# PSC_LED_KEYBOARD.net
KiCad netlist of a schematic drawn in Altium Designer
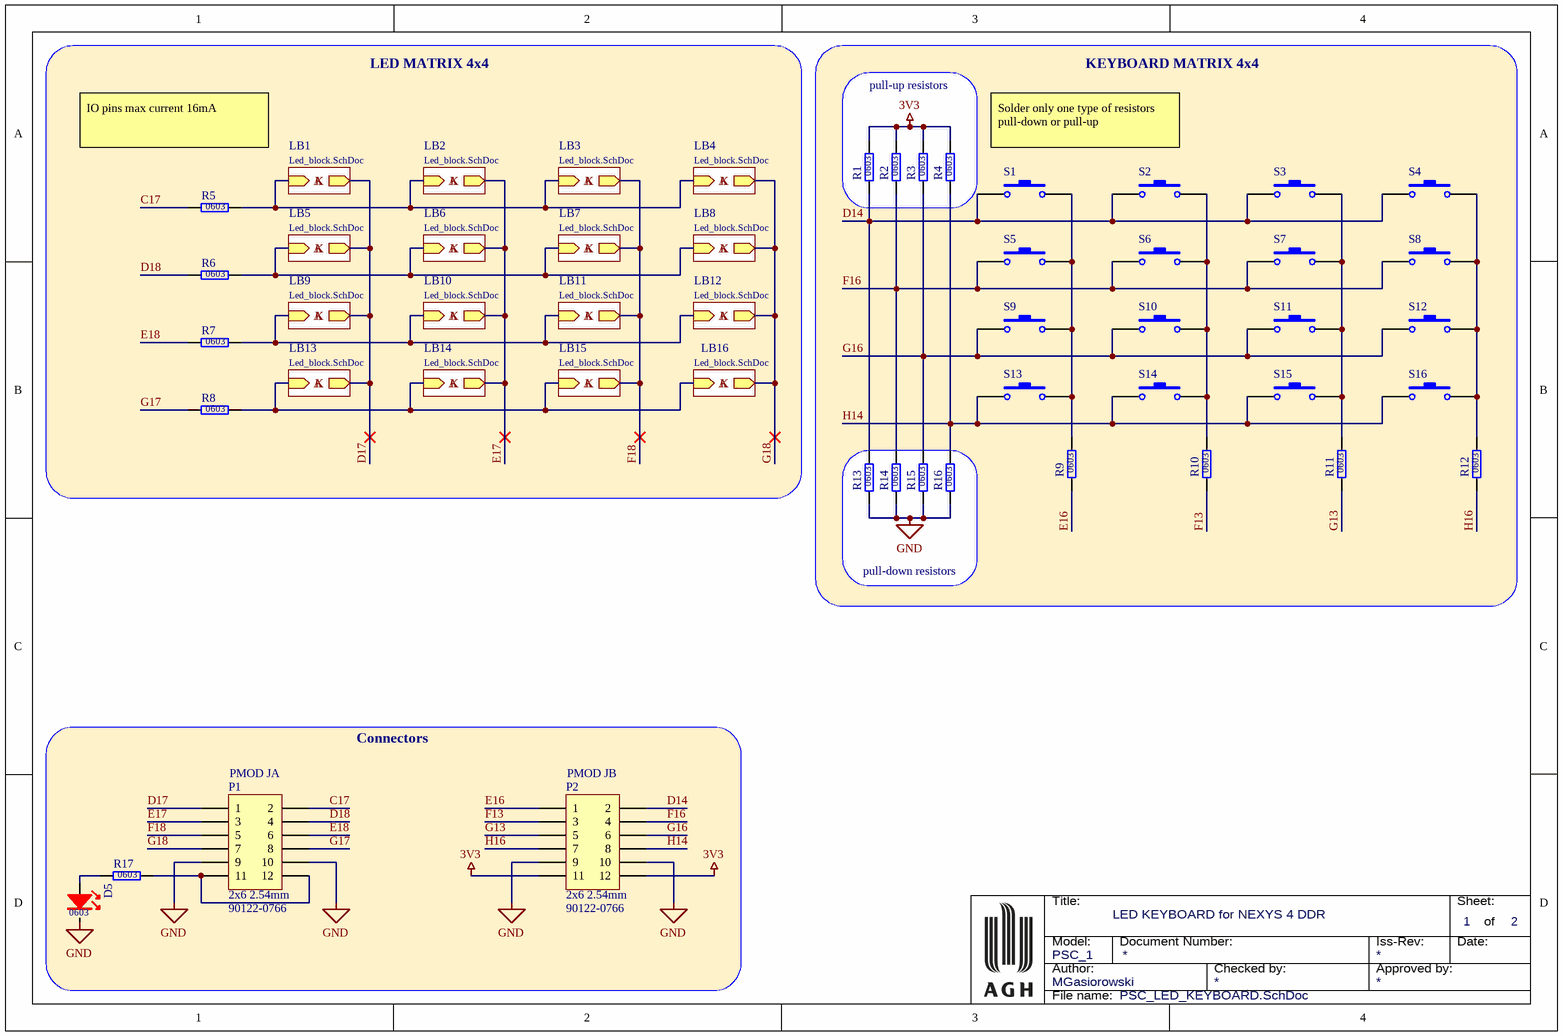
[diagram p0: PSC_LED_KEYBOARD.SchDoc]

(export (version "E")
  (design (tool "Eeschema 10.0.6"))
  (components
    (comp (ref "D5")
      (value "Red LED 0603")
      (footprint "OL_0603_1608")
      (description "LED_RED")
      (fields
        (field (name "SCH_FOOTPRINT") "0603")
        (field (name "PART NUMBER") "OL_R_0603_LTST-C193KRKT-5A")
        (field (name "MANUFACTURER") "Lite-On")
      )
      (libsource (lib "Library") (part "OL_R"))
    )
    (comp (ref "P1")
      (value "90122-0766")
      (footprint "P_HEADER_2x6_2.54_RIGHT_ANGLE")
      (description "Pin Header")
      (fields
        (field (name "SCH_FOOTPRINT") "2x6 2.54mm")
        (field (name "PART NUMBER") "P_HEADER_2x6_2.54_ANGLE")
        (field (name "MANUFACTURER") "Molex")
      )
      (libsource (lib "Library") (part "P_HEADER_2x6"))
    )
    (comp (ref "P2")
      (value "90122-0766")
      (footprint "P_HEADER_2x6_2.54_RIGHT_ANGLE")
      (description "Pin Header")
      (fields
        (field (name "SCH_FOOTPRINT") "2x6 2.54mm")
        (field (name "PART NUMBER") "P_HEADER_2x6_2.54_ANGLE")
        (field (name "MANUFACTURER") "Molex")
      )
      (libsource (lib "Library") (part "P_HEADER_2x6"))
    )
    (comp (ref "R1")
      (value "Resistor")
      (footprint "R_0603_1608")
      (fields
        (field (name "SCH_FOOTPRINT") "0603")
        (field (name "PART NUMBER") "R_10k_0603_0.1")
        (field (name "VOLTAGE") "75V")
        (field (name "POWER") "100mW")
      )
      (libsource (lib "Library") (part "R"))
    )
    (comp (ref "R2")
      (value "Resistor")
      (footprint "R_0603_1608")
      (fields
        (field (name "SCH_FOOTPRINT") "0603")
        (field (name "PART NUMBER") "R_10k_0603_0.1")
        (field (name "VOLTAGE") "75V")
        (field (name "POWER") "100mW")
      )
      (libsource (lib "Library") (part "R"))
    )
    (comp (ref "R3")
      (value "Resistor")
      (footprint "R_0603_1608")
      (fields
        (field (name "SCH_FOOTPRINT") "0603")
        (field (name "PART NUMBER") "R_10k_0603_0.1")
        (field (name "VOLTAGE") "75V")
        (field (name "POWER") "100mW")
      )
      (libsource (lib "Library") (part "R"))
    )
    (comp (ref "R4")
      (value "Resistor")
      (footprint "R_0603_1608")
      (fields
        (field (name "SCH_FOOTPRINT") "0603")
        (field (name "PART NUMBER") "R_10k_0603_0.1")
        (field (name "VOLTAGE") "75V")
        (field (name "POWER") "100mW")
      )
      (libsource (lib "Library") (part "R"))
    )
    (comp (ref "R5")
      (value "Resistor")
      (footprint "R_0603_1608")
      (fields
        (field (name "SCH_FOOTPRINT") "0603")
        (field (name "PART NUMBER") "R_10k_0603_0.1")
        (field (name "VOLTAGE") "75V")
        (field (name "POWER") "100mW")
      )
      (libsource (lib "Library") (part "R"))
    )
    (comp (ref "R6")
      (value "Resistor")
      (footprint "R_0603_1608")
      (fields
        (field (name "SCH_FOOTPRINT") "0603")
        (field (name "PART NUMBER") "R_10k_0603_0.1")
        (field (name "VOLTAGE") "75V")
        (field (name "POWER") "100mW")
      )
      (libsource (lib "Library") (part "R"))
    )
    (comp (ref "R7")
      (value "Resistor")
      (footprint "R_0603_1608")
      (fields
        (field (name "SCH_FOOTPRINT") "0603")
        (field (name "PART NUMBER") "R_10k_0603_0.1")
        (field (name "VOLTAGE") "75V")
        (field (name "POWER") "100mW")
      )
      (libsource (lib "Library") (part "R"))
    )
    (comp (ref "R8")
      (value "Resistor")
      (footprint "R_0603_1608")
      (fields
        (field (name "SCH_FOOTPRINT") "0603")
        (field (name "PART NUMBER") "R_10k_0603_0.1")
        (field (name "VOLTAGE") "75V")
        (field (name "POWER") "100mW")
      )
      (libsource (lib "Library") (part "R"))
    )
    (comp (ref "R9")
      (value "Resistor")
      (footprint "R_0603_1608")
      (fields
        (field (name "SCH_FOOTPRINT") "0603")
        (field (name "PART NUMBER") "R_10k_0603_0.1")
        (field (name "VOLTAGE") "75V")
        (field (name "POWER") "100mW")
      )
      (libsource (lib "Library") (part "R"))
    )
    (comp (ref "R10")
      (value "Resistor")
      (footprint "R_0603_1608")
      (fields
        (field (name "SCH_FOOTPRINT") "0603")
        (field (name "PART NUMBER") "R_10k_0603_0.1")
        (field (name "VOLTAGE") "75V")
        (field (name "POWER") "100mW")
      )
      (libsource (lib "Library") (part "R"))
    )
    (comp (ref "R11")
      (value "Resistor")
      (footprint "R_0603_1608")
      (fields
        (field (name "SCH_FOOTPRINT") "0603")
        (field (name "PART NUMBER") "R_10k_0603_0.1")
        (field (name "VOLTAGE") "75V")
        (field (name "POWER") "100mW")
      )
      (libsource (lib "Library") (part "R"))
    )
    (comp (ref "R12")
      (value "Resistor")
      (footprint "R_0603_1608")
      (fields
        (field (name "SCH_FOOTPRINT") "0603")
        (field (name "PART NUMBER") "R_10k_0603_0.1")
        (field (name "VOLTAGE") "75V")
        (field (name "POWER") "100mW")
      )
      (libsource (lib "Library") (part "R"))
    )
    (comp (ref "R13")
      (value "Resistor")
      (footprint "R_0603_1608")
      (fields
        (field (name "SCH_FOOTPRINT") "0603")
        (field (name "PART NUMBER") "R_10k_0603_0.1")
        (field (name "VOLTAGE") "75V")
        (field (name "POWER") "100mW")
      )
      (libsource (lib "Library") (part "R"))
    )
    (comp (ref "R14")
      (value "Resistor")
      (footprint "R_0603_1608")
      (fields
        (field (name "SCH_FOOTPRINT") "0603")
        (field (name "PART NUMBER") "R_10k_0603_0.1")
        (field (name "VOLTAGE") "75V")
        (field (name "POWER") "100mW")
      )
      (libsource (lib "Library") (part "R"))
    )
    (comp (ref "R15")
      (value "Resistor")
      (footprint "R_0603_1608")
      (fields
        (field (name "SCH_FOOTPRINT") "0603")
        (field (name "PART NUMBER") "R_10k_0603_0.1")
        (field (name "VOLTAGE") "75V")
        (field (name "POWER") "100mW")
      )
      (libsource (lib "Library") (part "R"))
    )
    (comp (ref "R16")
      (value "Resistor")
      (footprint "R_0603_1608")
      (fields
        (field (name "SCH_FOOTPRINT") "0603")
        (field (name "PART NUMBER") "R_10k_0603_0.1")
        (field (name "VOLTAGE") "75V")
        (field (name "POWER") "100mW")
      )
      (libsource (lib "Library") (part "R"))
    )
    (comp (ref "R17")
      (value "Resistor")
      (footprint "R_0603_1608")
      (fields
        (field (name "SCH_FOOTPRINT") "0603")
        (field (name "PART NUMBER") "R_10k_0603_0.1")
        (field (name "VOLTAGE") "75V")
        (field (name "POWER") "100mW")
      )
      (libsource (lib "Library") (part "R"))
    )
    (comp (ref "S1")
      (value "S_TACTSWITCH")
      (footprint "S_TactSwitch_12x12")
      (description "Tact switch")
      (libsource (lib "GG_LIB") (part "S_TACTSWITCH"))
    )
    (comp (ref "S2")
      (value "S_TACTSWITCH")
      (footprint "S_TactSwitch_12x12")
      (description "Tact switch")
      (libsource (lib "GG_LIB") (part "S_TACTSWITCH"))
    )
    (comp (ref "S3")
      (value "S_TACTSWITCH")
      (footprint "S_TactSwitch_12x12")
      (description "Tact switch")
      (libsource (lib "GG_LIB") (part "S_TACTSWITCH"))
    )
    (comp (ref "S4")
      (value "S_TACTSWITCH")
      (footprint "S_TactSwitch_12x12")
      (description "Tact switch")
      (libsource (lib "GG_LIB") (part "S_TACTSWITCH"))
    )
    (comp (ref "S5")
      (value "S_TACTSWITCH")
      (footprint "S_TactSwitch_12x12")
      (description "Tact switch")
      (libsource (lib "GG_LIB") (part "S_TACTSWITCH"))
    )
    (comp (ref "S6")
      (value "S_TACTSWITCH")
      (footprint "S_TactSwitch_12x12")
      (description "Tact switch")
      (libsource (lib "GG_LIB") (part "S_TACTSWITCH"))
    )
    (comp (ref "S7")
      (value "S_TACTSWITCH")
      (footprint "S_TactSwitch_12x12")
      (description "Tact switch")
      (libsource (lib "GG_LIB") (part "S_TACTSWITCH"))
    )
    (comp (ref "S8")
      (value "S_TACTSWITCH")
      (footprint "S_TactSwitch_12x12")
      (description "Tact switch")
      (libsource (lib "GG_LIB") (part "S_TACTSWITCH"))
    )
    (comp (ref "S9")
      (value "S_TACTSWITCH")
      (footprint "S_TactSwitch_12x12")
      (description "Tact switch")
      (libsource (lib "GG_LIB") (part "S_TACTSWITCH"))
    )
    (comp (ref "S10")
      (value "S_TACTSWITCH")
      (footprint "S_TactSwitch_12x12")
      (description "Tact switch")
      (libsource (lib "GG_LIB") (part "S_TACTSWITCH"))
    )
    (comp (ref "S11")
      (value "S_TACTSWITCH")
      (footprint "S_TactSwitch_12x12")
      (description "Tact switch")
      (libsource (lib "GG_LIB") (part "S_TACTSWITCH"))
    )
    (comp (ref "S12")
      (value "S_TACTSWITCH")
      (footprint "S_TactSwitch_12x12")
      (description "Tact switch")
      (libsource (lib "GG_LIB") (part "S_TACTSWITCH"))
    )
    (comp (ref "S13")
      (value "S_TACTSWITCH")
      (footprint "S_TactSwitch_12x12")
      (description "Tact switch")
      (libsource (lib "GG_LIB") (part "S_TACTSWITCH"))
    )
    (comp (ref "S14")
      (value "S_TACTSWITCH")
      (footprint "S_TactSwitch_12x12")
      (description "Tact switch")
      (libsource (lib "GG_LIB") (part "S_TACTSWITCH"))
    )
    (comp (ref "S15")
      (value "S_TACTSWITCH")
      (footprint "S_TactSwitch_12x12")
      (description "Tact switch")
      (libsource (lib "GG_LIB") (part "S_TACTSWITCH"))
    )
    (comp (ref "S16")
      (value "S_TACTSWITCH")
      (footprint "S_TactSwitch_12x12")
      (description "Tact switch")
      (libsource (lib "GG_LIB") (part "S_TACTSWITCH"))
    )
  )
  (nets
    (net (code "1") (name "/A") (class "Default")
      (node (ref "R8") (pin "2") (pinfunction "2_2") (pintype "passive"))
    )
    (net (code "2") (name "/A_1") (class "Default")
      (node (ref "R5") (pin "2") (pinfunction "2_2") (pintype "passive"))
    )
    (net (code "3") (name "/A_2") (class "Default")
      (node (ref "R6") (pin "2") (pinfunction "2_2") (pintype "passive"))
    )
    (net (code "4") (name "/A_3") (class "Default")
      (node (ref "R7") (pin "2") (pinfunction "2_2") (pintype "passive"))
    )
    (net (code "5") (name "/C17") (class "Default")
      (node (ref "P1") (pin "2") (pinfunction "2_2") (pintype "passive"))
      (node (ref "R5") (pin "1") (pinfunction "1_1") (pintype "passive"))
    )
    (net (code "6") (name "/D14") (class "Default")
      (node (ref "P2") (pin "2") (pinfunction "2_2") (pintype "passive"))
      (node (ref "R1") (pin "1") (pinfunction "1_1") (pintype "passive"))
      (node (ref "R13") (pin "2") (pinfunction "2_2") (pintype "passive"))
      (node (ref "S1") (pin "1") (pinfunction "1_1") (pintype "passive"))
      (node (ref "S2") (pin "1") (pinfunction "1_1") (pintype "passive"))
      (node (ref "S3") (pin "1") (pinfunction "1_1") (pintype "passive"))
      (node (ref "S4") (pin "1") (pinfunction "1_1") (pintype "passive"))
    )
    (net (code "7") (name "/D17") (class "Default")
      (node (ref "P1") (pin "1") (pinfunction "1_1") (pintype "passive"))
    )
    (net (code "8") (name "/D18") (class "Default")
      (node (ref "P1") (pin "4") (pinfunction "4_4") (pintype "passive"))
      (node (ref "R6") (pin "1") (pinfunction "1_1") (pintype "passive"))
    )
    (net (code "9") (name "/E16") (class "Default")
      (node (ref "P2") (pin "1") (pinfunction "1_1") (pintype "passive"))
      (node (ref "R9") (pin "1") (pinfunction "1_1") (pintype "passive"))
    )
    (net (code "10") (name "/E17") (class "Default")
      (node (ref "P1") (pin "3") (pinfunction "3_3") (pintype "passive"))
    )
    (net (code "11") (name "/E18") (class "Default")
      (node (ref "P1") (pin "6") (pinfunction "6_6") (pintype "passive"))
      (node (ref "R7") (pin "1") (pinfunction "1_1") (pintype "passive"))
    )
    (net (code "12") (name "/F13") (class "Default")
      (node (ref "P2") (pin "3") (pinfunction "3_3") (pintype "passive"))
      (node (ref "R10") (pin "1") (pinfunction "1_1") (pintype "passive"))
    )
    (net (code "13") (name "/F16") (class "Default")
      (node (ref "P2") (pin "4") (pinfunction "4_4") (pintype "passive"))
      (node (ref "R14") (pin "2") (pinfunction "2_2") (pintype "passive"))
      (node (ref "R2") (pin "1") (pinfunction "1_1") (pintype "passive"))
      (node (ref "S5") (pin "1") (pinfunction "1_1") (pintype "passive"))
      (node (ref "S6") (pin "1") (pinfunction "1_1") (pintype "passive"))
      (node (ref "S7") (pin "1") (pinfunction "1_1") (pintype "passive"))
      (node (ref "S8") (pin "1") (pinfunction "1_1") (pintype "passive"))
    )
    (net (code "14") (name "/F18") (class "Default")
      (node (ref "P1") (pin "5") (pinfunction "5_5") (pintype "passive"))
    )
    (net (code "15") (name "/G13") (class "Default")
      (node (ref "P2") (pin "5") (pinfunction "5_5") (pintype "passive"))
      (node (ref "R11") (pin "1") (pinfunction "1_1") (pintype "passive"))
    )
    (net (code "16") (name "/G16") (class "Default")
      (node (ref "P2") (pin "6") (pinfunction "6_6") (pintype "passive"))
      (node (ref "R15") (pin "2") (pinfunction "2_2") (pintype "passive"))
      (node (ref "R3") (pin "1") (pinfunction "1_1") (pintype "passive"))
      (node (ref "S10") (pin "1") (pinfunction "1_1") (pintype "passive"))
      (node (ref "S11") (pin "1") (pinfunction "1_1") (pintype "passive"))
      (node (ref "S12") (pin "1") (pinfunction "1_1") (pintype "passive"))
      (node (ref "S9") (pin "1") (pinfunction "1_1") (pintype "passive"))
    )
    (net (code "17") (name "/G17") (class "Default")
      (node (ref "P1") (pin "8") (pinfunction "8_8") (pintype "passive"))
      (node (ref "R8") (pin "1") (pinfunction "1_1") (pintype "passive"))
    )
    (net (code "18") (name "/G18") (class "Default")
      (node (ref "P1") (pin "7") (pinfunction "7_7") (pintype "passive"))
    )
    (net (code "19") (name "/H14") (class "Default")
      (node (ref "P2") (pin "8") (pinfunction "8_8") (pintype "passive"))
      (node (ref "R16") (pin "2") (pinfunction "2_2") (pintype "passive"))
      (node (ref "R4") (pin "1") (pinfunction "1_1") (pintype "passive"))
      (node (ref "S13") (pin "1") (pinfunction "1_1") (pintype "passive"))
      (node (ref "S14") (pin "1") (pinfunction "1_1") (pintype "passive"))
      (node (ref "S15") (pin "1") (pinfunction "1_1") (pintype "passive"))
      (node (ref "S16") (pin "1") (pinfunction "1_1") (pintype "passive"))
    )
    (net (code "20") (name "/H16") (class "Default")
      (node (ref "P2") (pin "7") (pinfunction "7_7") (pintype "passive"))
      (node (ref "R12") (pin "1") (pinfunction "1_1") (pintype "passive"))
    )
    (net (code "21") (name "3V3") (class "Default")
      (node (ref "P2") (pin "11") (pinfunction "11_11") (pintype "passive"))
      (node (ref "P2") (pin "12") (pinfunction "12_12") (pintype "passive"))
      (node (ref "R1") (pin "2") (pinfunction "2_2") (pintype "passive"))
      (node (ref "R2") (pin "2") (pinfunction "2_2") (pintype "passive"))
      (node (ref "R3") (pin "2") (pinfunction "2_2") (pintype "passive"))
      (node (ref "R4") (pin "2") (pinfunction "2_2") (pintype "passive"))
    )
    (net (code "22") (name "GND") (class "Default")
      (node (ref "D5") (pin "1") (pinfunction "K_1") (pintype "passive"))
      (node (ref "P1") (pin "10") (pinfunction "10_10") (pintype "passive"))
      (node (ref "P1") (pin "9") (pinfunction "9_9") (pintype "passive"))
      (node (ref "P2") (pin "10") (pinfunction "10_10") (pintype "passive"))
      (node (ref "P2") (pin "9") (pinfunction "9_9") (pintype "passive"))
      (node (ref "R13") (pin "1") (pinfunction "1_1") (pintype "passive"))
      (node (ref "R14") (pin "1") (pinfunction "1_1") (pintype "passive"))
      (node (ref "R15") (pin "1") (pinfunction "1_1") (pintype "passive"))
      (node (ref "R16") (pin "1") (pinfunction "1_1") (pintype "passive"))
    )
    (net (code "23") (name "Net-(D5-A)") (class "Default")
      (node (ref "D5") (pin "2") (pinfunction "A_2") (pintype "passive"))
      (node (ref "R17") (pin "1") (pinfunction "1_1") (pintype "passive"))
    )
    (net (code "24") (name "Net-(P1-Pad11)") (class "Default")
      (node (ref "P1") (pin "11") (pinfunction "11_11") (pintype "passive"))
      (node (ref "P1") (pin "12") (pinfunction "12_12") (pintype "passive"))
      (node (ref "R17") (pin "2") (pinfunction "2_2") (pintype "passive"))
    )
    (net (code "25") (name "Net-(R9-Pad2)") (class "Default")
      (node (ref "R9") (pin "2") (pinfunction "2_2") (pintype "passive"))
      (node (ref "S1") (pin "2") (pinfunction "2_2") (pintype "passive"))
      (node (ref "S13") (pin "2") (pinfunction "2_2") (pintype "passive"))
      (node (ref "S5") (pin "2") (pinfunction "2_2") (pintype "passive"))
      (node (ref "S9") (pin "2") (pinfunction "2_2") (pintype "passive"))
    )
    (net (code "26") (name "Net-(R10-Pad2)") (class "Default")
      (node (ref "R10") (pin "2") (pinfunction "2_2") (pintype "passive"))
      (node (ref "S10") (pin "2") (pinfunction "2_2") (pintype "passive"))
      (node (ref "S14") (pin "2") (pinfunction "2_2") (pintype "passive"))
      (node (ref "S2") (pin "2") (pinfunction "2_2") (pintype "passive"))
      (node (ref "S6") (pin "2") (pinfunction "2_2") (pintype "passive"))
    )
    (net (code "27") (name "Net-(R11-Pad2)") (class "Default")
      (node (ref "R11") (pin "2") (pinfunction "2_2") (pintype "passive"))
      (node (ref "S11") (pin "2") (pinfunction "2_2") (pintype "passive"))
      (node (ref "S15") (pin "2") (pinfunction "2_2") (pintype "passive"))
      (node (ref "S3") (pin "2") (pinfunction "2_2") (pintype "passive"))
      (node (ref "S7") (pin "2") (pinfunction "2_2") (pintype "passive"))
    )
    (net (code "28") (name "Net-(R12-Pad2)") (class "Default")
      (node (ref "R12") (pin "2") (pinfunction "2_2") (pintype "passive"))
      (node (ref "S12") (pin "2") (pinfunction "2_2") (pintype "passive"))
      (node (ref "S16") (pin "2") (pinfunction "2_2") (pintype "passive"))
      (node (ref "S4") (pin "2") (pinfunction "2_2") (pintype "passive"))
      (node (ref "S8") (pin "2") (pinfunction "2_2") (pintype "passive"))
    )
  )
)
